# base.net
KiCad netlist of a schematic drawn in EAGLE
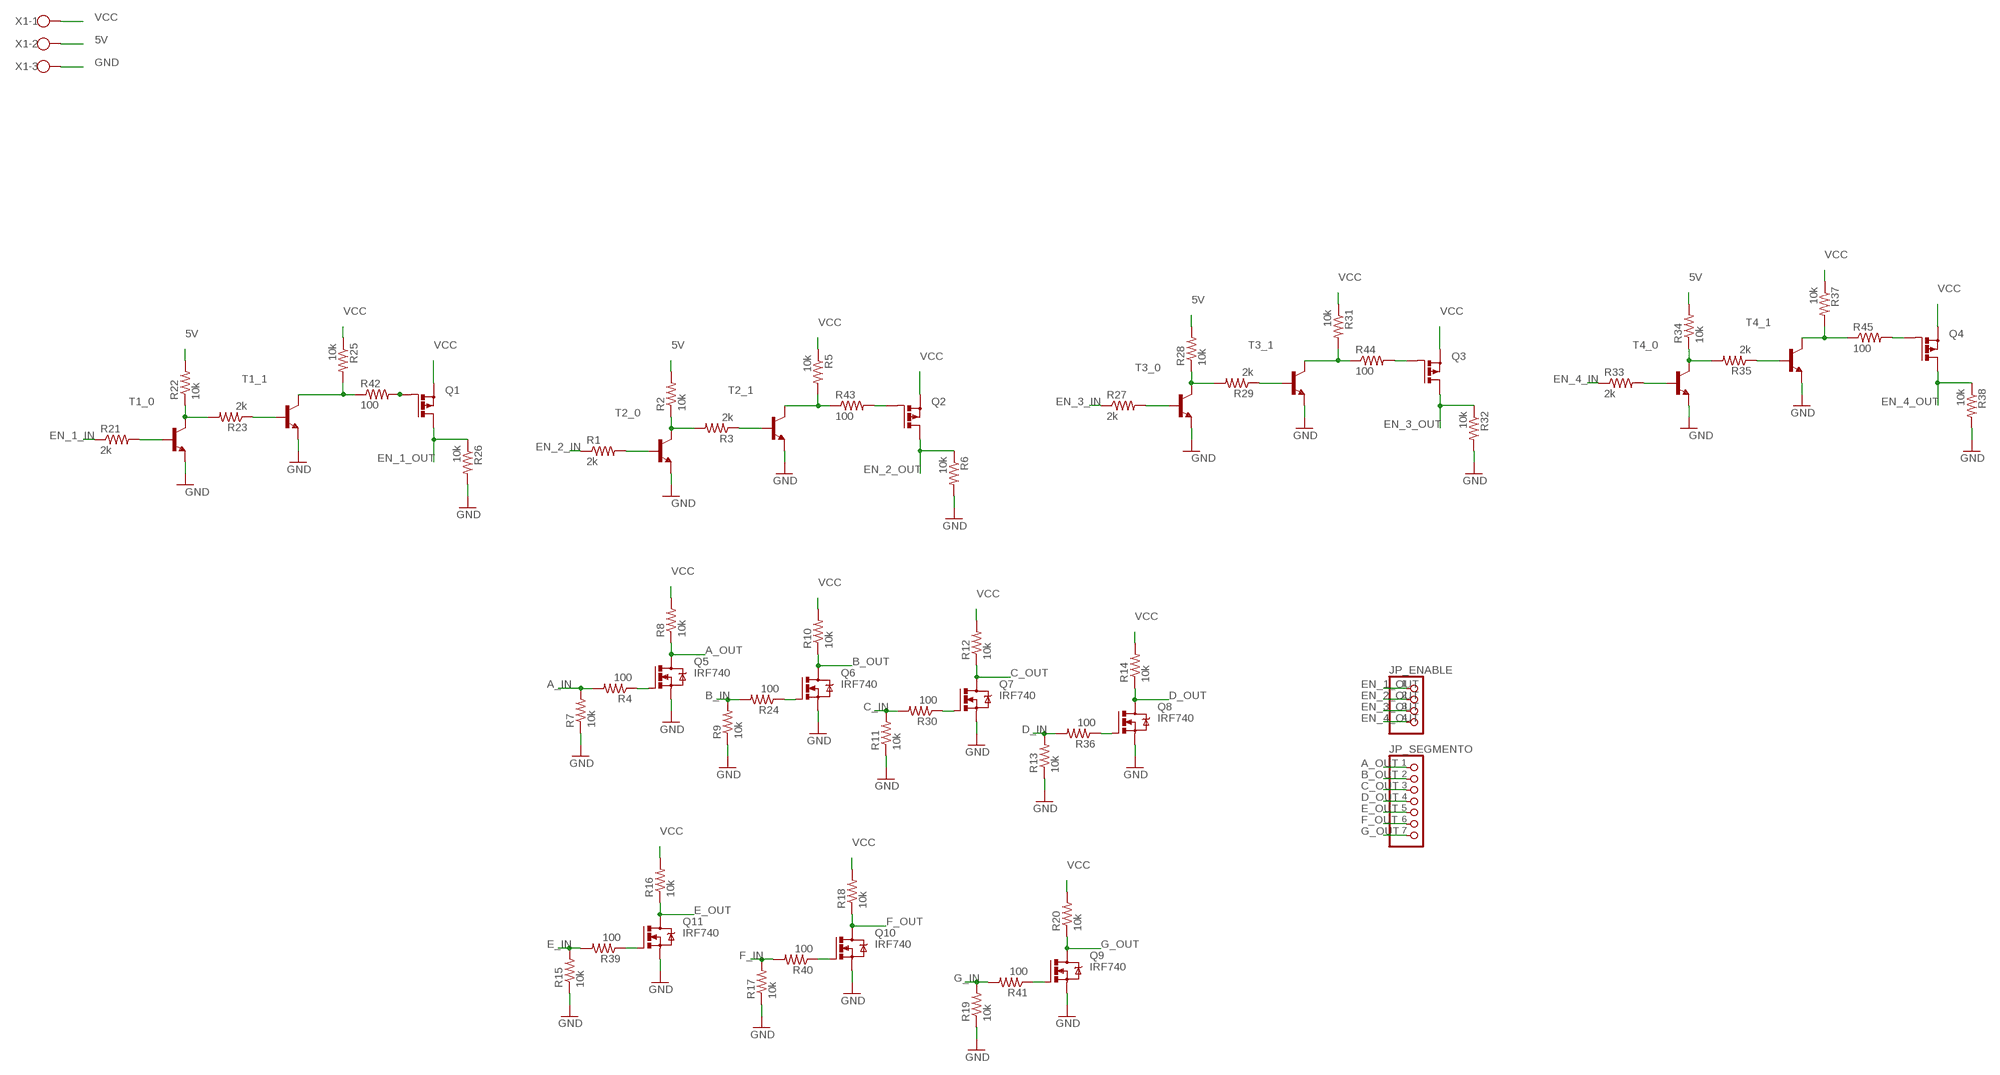
[diagram p0: schematic, sheet 1]

(export (version "E")
  (design (tool "Eeschema 10.0.6"))
  (components
    (comp (ref "JP_ENABLE")
      (value "PINHD-1X4")
      (footprint "eagle-import:1X04")
      (libsource (lib "eagle-import") (part "PINHD-1X4"))
    )
    (comp (ref "JP_SEGMENTO")
      (value "PINHD-1X7")
      (footprint "eagle-import:1X07")
      (libsource (lib "eagle-import") (part "PINHD-1X7"))
    )
    (comp (ref "Q1")
      (value "PMOSFET_PTO220BV")
      (footprint "eagle-import:TO220BV")
      (libsource (lib "eagle-import") (part "PMOSFET_PTO220BV"))
    )
    (comp (ref "Q2")
      (value "PMOSFET_PTO220BV")
      (footprint "eagle-import:TO220BV")
      (libsource (lib "eagle-import") (part "PMOSFET_PTO220BV"))
    )
    (comp (ref "Q3")
      (value "PMOSFET_PTO220BV")
      (footprint "eagle-import:TO220BV")
      (libsource (lib "eagle-import") (part "PMOSFET_PTO220BV"))
    )
    (comp (ref "Q4")
      (value "PMOSFET_PTO220BV")
      (footprint "eagle-import:TO220BV")
      (libsource (lib "eagle-import") (part "PMOSFET_PTO220BV"))
    )
    (comp (ref "Q5")
      (value "IRF740")
      (footprint "eagle-import:TO220BV")
      (libsource (lib "eagle-import") (part "IRF740"))
    )
    (comp (ref "Q6")
      (value "IRF740")
      (footprint "eagle-import:TO220BV")
      (libsource (lib "eagle-import") (part "IRF740"))
    )
    (comp (ref "Q7")
      (value "IRF740")
      (footprint "eagle-import:TO220BV")
      (libsource (lib "eagle-import") (part "IRF740"))
    )
    (comp (ref "Q8")
      (value "IRF740")
      (footprint "eagle-import:TO220BV")
      (libsource (lib "eagle-import") (part "IRF740"))
    )
    (comp (ref "Q9")
      (value "IRF740")
      (footprint "eagle-import:TO220BV")
      (libsource (lib "eagle-import") (part "IRF740"))
    )
    (comp (ref "Q10")
      (value "IRF740")
      (footprint "eagle-import:TO220BV")
      (libsource (lib "eagle-import") (part "IRF740"))
    )
    (comp (ref "Q11")
      (value "IRF740")
      (footprint "eagle-import:TO220BV")
      (libsource (lib "eagle-import") (part "IRF740"))
    )
    (comp (ref "R1")
      (value "2k")
      (footprint "eagle-import:0207_10")
      (libsource (lib "eagle-import") (part "R-US_0207/10"))
    )
    (comp (ref "R2")
      (value "10k")
      (footprint "eagle-import:0207_10")
      (libsource (lib "eagle-import") (part "R-US_0207/10"))
    )
    (comp (ref "R3")
      (value "2k")
      (footprint "eagle-import:0207_10")
      (libsource (lib "eagle-import") (part "R-US_0207/10"))
    )
    (comp (ref "R4")
      (value "100")
      (footprint "eagle-import:0207_10")
      (libsource (lib "eagle-import") (part "R-US_0207/10"))
    )
    (comp (ref "R5")
      (value "10k")
      (footprint "eagle-import:0207_10")
      (libsource (lib "eagle-import") (part "R-US_0207/10"))
    )
    (comp (ref "R6")
      (value "10k")
      (footprint "eagle-import:0207_10")
      (libsource (lib "eagle-import") (part "R-US_0207/10"))
    )
    (comp (ref "R7")
      (value "10k")
      (footprint "eagle-import:0207_10")
      (libsource (lib "eagle-import") (part "R-US_0207/10"))
    )
    (comp (ref "R8")
      (value "10k")
      (footprint "eagle-import:0207_10")
      (libsource (lib "eagle-import") (part "R-US_0207/10"))
    )
    (comp (ref "R9")
      (value "10k")
      (footprint "eagle-import:0207_10")
      (libsource (lib "eagle-import") (part "R-US_0207/10"))
    )
    (comp (ref "R10")
      (value "10k")
      (footprint "eagle-import:0207_10")
      (libsource (lib "eagle-import") (part "R-US_0207/10"))
    )
    (comp (ref "R11")
      (value "10k")
      (footprint "eagle-import:0207_10")
      (libsource (lib "eagle-import") (part "R-US_0207/10"))
    )
    (comp (ref "R12")
      (value "10k")
      (footprint "eagle-import:0207_10")
      (libsource (lib "eagle-import") (part "R-US_0207/10"))
    )
    (comp (ref "R13")
      (value "10k")
      (footprint "eagle-import:0207_10")
      (libsource (lib "eagle-import") (part "R-US_0207/10"))
    )
    (comp (ref "R14")
      (value "10k")
      (footprint "eagle-import:0207_10")
      (libsource (lib "eagle-import") (part "R-US_0207/10"))
    )
    (comp (ref "R15")
      (value "10k")
      (footprint "eagle-import:0207_10")
      (libsource (lib "eagle-import") (part "R-US_0207/10"))
    )
    (comp (ref "R16")
      (value "10k")
      (footprint "eagle-import:0207_10")
      (libsource (lib "eagle-import") (part "R-US_0207/10"))
    )
    (comp (ref "R17")
      (value "10k")
      (footprint "eagle-import:0207_10")
      (libsource (lib "eagle-import") (part "R-US_0207/10"))
    )
    (comp (ref "R18")
      (value "10k")
      (footprint "eagle-import:0207_10")
      (libsource (lib "eagle-import") (part "R-US_0207/10"))
    )
    (comp (ref "R19")
      (value "10k")
      (footprint "eagle-import:0207_10")
      (libsource (lib "eagle-import") (part "R-US_0207/10"))
    )
    (comp (ref "R20")
      (value "10k")
      (footprint "eagle-import:0207_10")
      (libsource (lib "eagle-import") (part "R-US_0207/10"))
    )
    (comp (ref "R21")
      (value "2k")
      (footprint "eagle-import:0207_10")
      (libsource (lib "eagle-import") (part "R-US_0207/10"))
    )
    (comp (ref "R22")
      (value "10k")
      (footprint "eagle-import:0207_10")
      (libsource (lib "eagle-import") (part "R-US_0207/10"))
    )
    (comp (ref "R23")
      (value "2k")
      (footprint "eagle-import:0207_10")
      (libsource (lib "eagle-import") (part "R-US_0207/10"))
    )
    (comp (ref "R24")
      (value "100")
      (footprint "eagle-import:0207_10")
      (libsource (lib "eagle-import") (part "R-US_0207/10"))
    )
    (comp (ref "R25")
      (value "10k")
      (footprint "eagle-import:0207_10")
      (libsource (lib "eagle-import") (part "R-US_0207/10"))
    )
    (comp (ref "R26")
      (value "10k")
      (footprint "eagle-import:0207_10")
      (libsource (lib "eagle-import") (part "R-US_0207/10"))
    )
    (comp (ref "R27")
      (value "2k")
      (footprint "eagle-import:0207_10")
      (libsource (lib "eagle-import") (part "R-US_0207/10"))
    )
    (comp (ref "R28")
      (value "10k")
      (footprint "eagle-import:0207_10")
      (libsource (lib "eagle-import") (part "R-US_0207/10"))
    )
    (comp (ref "R29")
      (value "2k")
      (footprint "eagle-import:0207_10")
      (libsource (lib "eagle-import") (part "R-US_0207/10"))
    )
    (comp (ref "R30")
      (value "100")
      (footprint "eagle-import:0207_10")
      (libsource (lib "eagle-import") (part "R-US_0207/10"))
    )
    (comp (ref "R31")
      (value "10k")
      (footprint "eagle-import:0207_10")
      (libsource (lib "eagle-import") (part "R-US_0207/10"))
    )
    (comp (ref "R32")
      (value "10k")
      (footprint "eagle-import:0207_10")
      (libsource (lib "eagle-import") (part "R-US_0207/10"))
    )
    (comp (ref "R33")
      (value "2k")
      (footprint "eagle-import:0207_10")
      (libsource (lib "eagle-import") (part "R-US_0207/10"))
    )
    (comp (ref "R34")
      (value "10k")
      (footprint "eagle-import:0207_10")
      (libsource (lib "eagle-import") (part "R-US_0207/10"))
    )
    (comp (ref "R35")
      (value "2k")
      (footprint "eagle-import:0207_10")
      (libsource (lib "eagle-import") (part "R-US_0207/10"))
    )
    (comp (ref "R36")
      (value "100")
      (footprint "eagle-import:0207_10")
      (libsource (lib "eagle-import") (part "R-US_0207/10"))
    )
    (comp (ref "R37")
      (value "10k")
      (footprint "eagle-import:0207_10")
      (libsource (lib "eagle-import") (part "R-US_0207/10"))
    )
    (comp (ref "R38")
      (value "10k")
      (footprint "eagle-import:0207_10")
      (libsource (lib "eagle-import") (part "R-US_0207/10"))
    )
    (comp (ref "R39")
      (value "100")
      (footprint "eagle-import:0207_10")
      (libsource (lib "eagle-import") (part "R-US_0207/10"))
    )
    (comp (ref "R40")
      (value "100")
      (footprint "eagle-import:0207_10")
      (libsource (lib "eagle-import") (part "R-US_0207/10"))
    )
    (comp (ref "R41")
      (value "100")
      (footprint "eagle-import:0207_10")
      (libsource (lib "eagle-import") (part "R-US_0207/10"))
    )
    (comp (ref "R42")
      (value "100")
      (footprint "eagle-import:0207_10")
      (libsource (lib "eagle-import") (part "R-US_0207/10"))
    )
    (comp (ref "R43")
      (value "100")
      (footprint "eagle-import:0207_10")
      (libsource (lib "eagle-import") (part "R-US_0207/10"))
    )
    (comp (ref "R44")
      (value "100")
      (footprint "eagle-import:0207_10")
      (libsource (lib "eagle-import") (part "R-US_0207/10"))
    )
    (comp (ref "R45")
      (value "100")
      (footprint "eagle-import:0207_10")
      (libsource (lib "eagle-import") (part "R-US_0207/10"))
    )
    (comp (ref "T1_0")
      (value "2N2222-NPN-TO92-EBC")
      (footprint "eagle-import:TO92-EBC")
      (libsource (lib "eagle-import") (part "-NPN-TO92-EBC2N2222"))
    )
    (comp (ref "T1_1")
      (value "2N2222-NPN-TO92-EBC")
      (footprint "eagle-import:TO92-EBC")
      (libsource (lib "eagle-import") (part "-NPN-TO92-EBC2N2222"))
    )
    (comp (ref "T2_0")
      (value "2N2222-NPN-TO92-EBC")
      (footprint "eagle-import:TO92-EBC")
      (libsource (lib "eagle-import") (part "-NPN-TO92-EBC2N2222"))
    )
    (comp (ref "T2_1")
      (value "2N2222-NPN-TO92-EBC")
      (footprint "eagle-import:TO92-EBC")
      (libsource (lib "eagle-import") (part "-NPN-TO92-EBC2N2222"))
    )
    (comp (ref "T3_0")
      (value "2N2222-NPN-TO92-EBC")
      (footprint "eagle-import:TO92-EBC")
      (libsource (lib "eagle-import") (part "-NPN-TO92-EBC2N2222"))
    )
    (comp (ref "T3_1")
      (value "2N2222-NPN-TO92-EBC")
      (footprint "eagle-import:TO92-EBC")
      (libsource (lib "eagle-import") (part "-NPN-TO92-EBC2N2222"))
    )
    (comp (ref "T4_0")
      (value "2N2222-NPN-TO92-EBC")
      (footprint "eagle-import:TO92-EBC")
      (libsource (lib "eagle-import") (part "-NPN-TO92-EBC2N2222"))
    )
    (comp (ref "T4_1")
      (value "2N2222-NPN-TO92-EBC")
      (footprint "eagle-import:TO92-EBC")
      (libsource (lib "eagle-import") (part "-NPN-TO92-EBC2N2222"))
    )
    (comp (ref "X1")
      (value "W237-103")
      (footprint "eagle-import:W237-103")
      (fields (field (name "MPN") "237-103"))
      (libsource (lib "eagle-import") (part "W237-103"))
    )
  )
  (nets
    (net (code "1") (name "/5V") (class "Default")
      (node (ref "R2") (pin "2") (pinfunction "2_2") (pintype "passive"))
      (node (ref "R22") (pin "2") (pinfunction "2_2") (pintype "passive"))
      (node (ref "R28") (pin "2") (pinfunction "2_2") (pintype "passive"))
      (node (ref "R34") (pin "2") (pinfunction "2_2") (pintype "passive"))
      (node (ref "X1") (pin "2") (pinfunction "KL_2") (pintype "passive"))
    )
    (net (code "2") (name "/A_IN") (class "Default")
      (node (ref "R4") (pin "2") (pinfunction "2_2") (pintype "passive"))
      (node (ref "R7") (pin "2") (pinfunction "2_2") (pintype "passive"))
    )
    (net (code "3") (name "/A_OUT") (class "Default")
      (node (ref "JP_SEGMENTO") (pin "1") (pinfunction "1_1") (pintype "passive"))
      (node (ref "Q5") (pin "D") (pinfunction "D_D") (pintype "passive"))
      (node (ref "R8") (pin "1") (pinfunction "1_1") (pintype "passive"))
    )
    (net (code "4") (name "/B_IN") (class "Default")
      (node (ref "R24") (pin "2") (pinfunction "2_2") (pintype "passive"))
      (node (ref "R9") (pin "2") (pinfunction "2_2") (pintype "passive"))
    )
    (net (code "5") (name "/B_OUT") (class "Default")
      (node (ref "JP_SEGMENTO") (pin "2") (pinfunction "2_2") (pintype "passive"))
      (node (ref "Q6") (pin "D") (pinfunction "D_D") (pintype "passive"))
      (node (ref "R10") (pin "1") (pinfunction "1_1") (pintype "passive"))
    )
    (net (code "6") (name "/C_IN") (class "Default")
      (node (ref "R11") (pin "2") (pinfunction "2_2") (pintype "passive"))
      (node (ref "R30") (pin "2") (pinfunction "2_2") (pintype "passive"))
    )
    (net (code "7") (name "/C_OUT") (class "Default")
      (node (ref "JP_SEGMENTO") (pin "3") (pinfunction "3_3") (pintype "passive"))
      (node (ref "Q7") (pin "D") (pinfunction "D_D") (pintype "passive"))
      (node (ref "R12") (pin "1") (pinfunction "1_1") (pintype "passive"))
    )
    (net (code "8") (name "/D_IN") (class "Default")
      (node (ref "R13") (pin "2") (pinfunction "2_2") (pintype "passive"))
      (node (ref "R36") (pin "2") (pinfunction "2_2") (pintype "passive"))
    )
    (net (code "9") (name "/D_OUT") (class "Default")
      (node (ref "JP_SEGMENTO") (pin "4") (pinfunction "4_4") (pintype "passive"))
      (node (ref "Q8") (pin "D") (pinfunction "D_D") (pintype "passive"))
      (node (ref "R14") (pin "1") (pinfunction "1_1") (pintype "passive"))
    )
    (net (code "10") (name "/EN_1_IN") (class "Default")
      (node (ref "R21") (pin "1") (pinfunction "1_1") (pintype "passive"))
    )
    (net (code "11") (name "/EN_1_OUT") (class "Default")
      (node (ref "JP_ENABLE") (pin "1") (pinfunction "1_1") (pintype "passive"))
      (node (ref "Q1") (pin "D") (pinfunction "D_D") (pintype "passive"))
      (node (ref "R26") (pin "1") (pinfunction "1_1") (pintype "passive"))
    )
    (net (code "12") (name "/EN_2_IN") (class "Default")
      (node (ref "R1") (pin "1") (pinfunction "1_1") (pintype "passive"))
    )
    (net (code "13") (name "/EN_2_OUT") (class "Default")
      (node (ref "JP_ENABLE") (pin "2") (pinfunction "2_2") (pintype "passive"))
      (node (ref "Q2") (pin "D") (pinfunction "D_D") (pintype "passive"))
      (node (ref "R6") (pin "1") (pinfunction "1_1") (pintype "passive"))
    )
    (net (code "14") (name "/EN_3_IN") (class "Default")
      (node (ref "R27") (pin "1") (pinfunction "1_1") (pintype "passive"))
    )
    (net (code "15") (name "/EN_3_OUT") (class "Default")
      (node (ref "JP_ENABLE") (pin "3") (pinfunction "3_3") (pintype "passive"))
      (node (ref "Q3") (pin "D") (pinfunction "D_D") (pintype "passive"))
      (node (ref "R32") (pin "1") (pinfunction "1_1") (pintype "passive"))
    )
    (net (code "16") (name "/EN_4_IN") (class "Default")
      (node (ref "R33") (pin "1") (pinfunction "1_1") (pintype "passive"))
    )
    (net (code "17") (name "/EN_4_OUT") (class "Default")
      (node (ref "JP_ENABLE") (pin "4") (pinfunction "4_4") (pintype "passive"))
      (node (ref "Q4") (pin "D") (pinfunction "D_D") (pintype "passive"))
      (node (ref "R38") (pin "1") (pinfunction "1_1") (pintype "passive"))
    )
    (net (code "18") (name "/E_IN") (class "Default")
      (node (ref "R15") (pin "2") (pinfunction "2_2") (pintype "passive"))
      (node (ref "R39") (pin "2") (pinfunction "2_2") (pintype "passive"))
    )
    (net (code "19") (name "/E_OUT") (class "Default")
      (node (ref "JP_SEGMENTO") (pin "5") (pinfunction "5_5") (pintype "passive"))
      (node (ref "Q11") (pin "D") (pinfunction "D_D") (pintype "passive"))
      (node (ref "R16") (pin "1") (pinfunction "1_1") (pintype "passive"))
    )
    (net (code "20") (name "/F_IN") (class "Default")
      (node (ref "R17") (pin "2") (pinfunction "2_2") (pintype "passive"))
      (node (ref "R40") (pin "2") (pinfunction "2_2") (pintype "passive"))
    )
    (net (code "21") (name "/F_OUT") (class "Default")
      (node (ref "JP_SEGMENTO") (pin "6") (pinfunction "6_6") (pintype "passive"))
      (node (ref "Q10") (pin "D") (pinfunction "D_D") (pintype "passive"))
      (node (ref "R18") (pin "1") (pinfunction "1_1") (pintype "passive"))
    )
    (net (code "22") (name "/G_IN") (class "Default")
      (node (ref "R19") (pin "2") (pinfunction "2_2") (pintype "passive"))
      (node (ref "R41") (pin "2") (pinfunction "2_2") (pintype "passive"))
    )
    (net (code "23") (name "/G_OUT") (class "Default")
      (node (ref "JP_SEGMENTO") (pin "7") (pinfunction "7_7") (pintype "passive"))
      (node (ref "Q9") (pin "D") (pinfunction "D_D") (pintype "passive"))
      (node (ref "R20") (pin "1") (pinfunction "1_1") (pintype "passive"))
    )
    (net (code "24") (name "/VCC") (class "Default")
      (node (ref "Q1") (pin "S") (pinfunction "S_S") (pintype "passive"))
      (node (ref "Q2") (pin "S") (pinfunction "S_S") (pintype "passive"))
      (node (ref "Q3") (pin "S") (pinfunction "S_S") (pintype "passive"))
      (node (ref "Q4") (pin "S") (pinfunction "S_S") (pintype "passive"))
      (node (ref "R10") (pin "2") (pinfunction "2_2") (pintype "passive"))
      (node (ref "R12") (pin "2") (pinfunction "2_2") (pintype "passive"))
      (node (ref "R14") (pin "2") (pinfunction "2_2") (pintype "passive"))
      (node (ref "R16") (pin "2") (pinfunction "2_2") (pintype "passive"))
      (node (ref "R18") (pin "2") (pinfunction "2_2") (pintype "passive"))
      (node (ref "R20") (pin "2") (pinfunction "2_2") (pintype "passive"))
      (node (ref "R25") (pin "1") (pinfunction "1_1") (pintype "passive"))
      (node (ref "R31") (pin "1") (pinfunction "1_1") (pintype "passive"))
      (node (ref "R37") (pin "1") (pinfunction "1_1") (pintype "passive"))
      (node (ref "R5") (pin "1") (pinfunction "1_1") (pintype "passive"))
      (node (ref "R8") (pin "2") (pinfunction "2_2") (pintype "passive"))
      (node (ref "X1") (pin "1") (pinfunction "KL_1") (pintype "passive"))
    )
    (net (code "25") (name "GND") (class "Default")
      (node (ref "Q10") (pin "S") (pinfunction "S_S") (pintype "passive"))
      (node (ref "Q11") (pin "S") (pinfunction "S_S") (pintype "passive"))
      (node (ref "Q5") (pin "S") (pinfunction "S_S") (pintype "passive"))
      (node (ref "Q6") (pin "S") (pinfunction "S_S") (pintype "passive"))
      (node (ref "Q7") (pin "S") (pinfunction "S_S") (pintype "passive"))
      (node (ref "Q8") (pin "S") (pinfunction "S_S") (pintype "passive"))
      (node (ref "Q9") (pin "S") (pinfunction "S_S") (pintype "passive"))
      (node (ref "R11") (pin "1") (pinfunction "1_1") (pintype "passive"))
      (node (ref "R13") (pin "1") (pinfunction "1_1") (pintype "passive"))
      (node (ref "R15") (pin "1") (pinfunction "1_1") (pintype "passive"))
      (node (ref "R17") (pin "1") (pinfunction "1_1") (pintype "passive"))
      (node (ref "R19") (pin "1") (pinfunction "1_1") (pintype "passive"))
      (node (ref "R26") (pin "2") (pinfunction "2_2") (pintype "passive"))
      (node (ref "R32") (pin "2") (pinfunction "2_2") (pintype "passive"))
      (node (ref "R38") (pin "2") (pinfunction "2_2") (pintype "passive"))
      (node (ref "R6") (pin "2") (pinfunction "2_2") (pintype "passive"))
      (node (ref "R7") (pin "1") (pinfunction "1_1") (pintype "passive"))
      (node (ref "R9") (pin "1") (pinfunction "1_1") (pintype "passive"))
      (node (ref "T1_0") (pin "E") (pinfunction "E_E") (pintype "passive"))
      (node (ref "T1_1") (pin "E") (pinfunction "E_E") (pintype "passive"))
      (node (ref "T2_0") (pin "E") (pinfunction "E_E") (pintype "passive"))
      (node (ref "T2_1") (pin "E") (pinfunction "E_E") (pintype "passive"))
      (node (ref "T3_0") (pin "E") (pinfunction "E_E") (pintype "passive"))
      (node (ref "T3_1") (pin "E") (pinfunction "E_E") (pintype "passive"))
      (node (ref "T4_0") (pin "E") (pinfunction "E_E") (pintype "passive"))
      (node (ref "T4_1") (pin "E") (pinfunction "E_E") (pintype "passive"))
      (node (ref "X1") (pin "3") (pinfunction "KL_3") (pintype "passive"))
    )
    (net (code "26") (name "Net-(Q1-PadG)") (class "Default")
      (node (ref "Q1") (pin "G") (pinfunction "G_G") (pintype "passive"))
      (node (ref "R42") (pin "2") (pinfunction "2_2") (pintype "passive"))
    )
    (net (code "27") (name "Net-(Q2-PadG)") (class "Default")
      (node (ref "Q2") (pin "G") (pinfunction "G_G") (pintype "passive"))
      (node (ref "R43") (pin "2") (pinfunction "2_2") (pintype "passive"))
    )
    (net (code "28") (name "Net-(Q3-PadG)") (class "Default")
      (node (ref "Q3") (pin "G") (pinfunction "G_G") (pintype "passive"))
      (node (ref "R44") (pin "2") (pinfunction "2_2") (pintype "passive"))
    )
    (net (code "29") (name "Net-(Q4-PadG)") (class "Default")
      (node (ref "Q4") (pin "G") (pinfunction "G_G") (pintype "passive"))
      (node (ref "R45") (pin "2") (pinfunction "2_2") (pintype "passive"))
    )
    (net (code "30") (name "Net-(Q5-PadG)") (class "Default")
      (node (ref "Q5") (pin "G") (pinfunction "G_G") (pintype "passive"))
      (node (ref "R4") (pin "1") (pinfunction "1_1") (pintype "passive"))
    )
    (net (code "31") (name "Net-(Q6-PadG)") (class "Default")
      (node (ref "Q6") (pin "G") (pinfunction "G_G") (pintype "passive"))
      (node (ref "R24") (pin "1") (pinfunction "1_1") (pintype "passive"))
    )
    (net (code "32") (name "Net-(Q7-PadG)") (class "Default")
      (node (ref "Q7") (pin "G") (pinfunction "G_G") (pintype "passive"))
      (node (ref "R30") (pin "1") (pinfunction "1_1") (pintype "passive"))
    )
    (net (code "33") (name "Net-(Q8-PadG)") (class "Default")
      (node (ref "Q8") (pin "G") (pinfunction "G_G") (pintype "passive"))
      (node (ref "R36") (pin "1") (pinfunction "1_1") (pintype "passive"))
    )
    (net (code "34") (name "Net-(Q9-PadG)") (class "Default")
      (node (ref "Q9") (pin "G") (pinfunction "G_G") (pintype "passive"))
      (node (ref "R41") (pin "1") (pinfunction "1_1") (pintype "passive"))
    )
    (net (code "35") (name "Net-(Q10-PadG)") (class "Default")
      (node (ref "Q10") (pin "G") (pinfunction "G_G") (pintype "passive"))
      (node (ref "R40") (pin "1") (pinfunction "1_1") (pintype "passive"))
    )
    (net (code "36") (name "Net-(Q11-PadG)") (class "Default")
      (node (ref "Q11") (pin "G") (pinfunction "G_G") (pintype "passive"))
      (node (ref "R39") (pin "1") (pinfunction "1_1") (pintype "passive"))
    )
    (net (code "37") (name "Net-(R1-Pad2)") (class "Default")
      (node (ref "R1") (pin "2") (pinfunction "2_2") (pintype "passive"))
      (node (ref "T2_0") (pin "B") (pinfunction "B_B") (pintype "passive"))
    )
    (net (code "38") (name "Net-(R2-Pad1)") (class "Default")
      (node (ref "R2") (pin "1") (pinfunction "1_1") (pintype "passive"))
      (node (ref "R3") (pin "2") (pinfunction "2_2") (pintype "passive"))
      (node (ref "T2_0") (pin "C") (pinfunction "C_C") (pintype "passive"))
    )
    (net (code "39") (name "Net-(R3-Pad1)") (class "Default")
      (node (ref "R3") (pin "1") (pinfunction "1_1") (pintype "passive"))
      (node (ref "T2_1") (pin "B") (pinfunction "B_B") (pintype "passive"))
    )
    (net (code "40") (name "Net-(R21-Pad2)") (class "Default")
      (node (ref "R21") (pin "2") (pinfunction "2_2") (pintype "passive"))
      (node (ref "T1_0") (pin "B") (pinfunction "B_B") (pintype "passive"))
    )
    (net (code "41") (name "Net-(R22-Pad1)") (class "Default")
      (node (ref "R22") (pin "1") (pinfunction "1_1") (pintype "passive"))
      (node (ref "R23") (pin "2") (pinfunction "2_2") (pintype "passive"))
      (node (ref "T1_0") (pin "C") (pinfunction "C_C") (pintype "passive"))
    )
    (net (code "42") (name "Net-(R23-Pad1)") (class "Default")
      (node (ref "R23") (pin "1") (pinfunction "1_1") (pintype "passive"))
      (node (ref "T1_1") (pin "B") (pinfunction "B_B") (pintype "passive"))
    )
    (net (code "43") (name "Net-(R25-Pad2)") (class "Default")
      (node (ref "R25") (pin "2") (pinfunction "2_2") (pintype "passive"))
      (node (ref "R42") (pin "1") (pinfunction "1_1") (pintype "passive"))
      (node (ref "T1_1") (pin "C") (pinfunction "C_C") (pintype "passive"))
    )
    (net (code "44") (name "Net-(R27-Pad2)") (class "Default")
      (node (ref "R27") (pin "2") (pinfunction "2_2") (pintype "passive"))
      (node (ref "T3_0") (pin "B") (pinfunction "B_B") (pintype "passive"))
    )
    (net (code "45") (name "Net-(R28-Pad1)") (class "Default")
      (node (ref "R28") (pin "1") (pinfunction "1_1") (pintype "passive"))
      (node (ref "R29") (pin "2") (pinfunction "2_2") (pintype "passive"))
      (node (ref "T3_0") (pin "C") (pinfunction "C_C") (pintype "passive"))
    )
    (net (code "46") (name "Net-(R29-Pad1)") (class "Default")
      (node (ref "R29") (pin "1") (pinfunction "1_1") (pintype "passive"))
      (node (ref "T3_1") (pin "B") (pinfunction "B_B") (pintype "passive"))
    )
    (net (code "47") (name "Net-(R31-Pad2)") (class "Default")
      (node (ref "R31") (pin "2") (pinfunction "2_2") (pintype "passive"))
      (node (ref "R44") (pin "1") (pinfunction "1_1") (pintype "passive"))
      (node (ref "T3_1") (pin "C") (pinfunction "C_C") (pintype "passive"))
    )
    (net (code "48") (name "Net-(R33-Pad2)") (class "Default")
      (node (ref "R33") (pin "2") (pinfunction "2_2") (pintype "passive"))
      (node (ref "T4_0") (pin "B") (pinfunction "B_B") (pintype "passive"))
    )
    (net (code "49") (name "Net-(R34-Pad1)") (class "Default")
      (node (ref "R34") (pin "1") (pinfunction "1_1") (pintype "passive"))
      (node (ref "R35") (pin "2") (pinfunction "2_2") (pintype "passive"))
      (node (ref "T4_0") (pin "C") (pinfunction "C_C") (pintype "passive"))
    )
    (net (code "50") (name "Net-(R35-Pad1)") (class "Default")
      (node (ref "R35") (pin "1") (pinfunction "1_1") (pintype "passive"))
      (node (ref "T4_1") (pin "B") (pinfunction "B_B") (pintype "passive"))
    )
    (net (code "51") (name "Net-(R37-Pad2)") (class "Default")
      (node (ref "R37") (pin "2") (pinfunction "2_2") (pintype "passive"))
      (node (ref "R45") (pin "1") (pinfunction "1_1") (pintype "passive"))
      (node (ref "T4_1") (pin "C") (pinfunction "C_C") (pintype "passive"))
    )
    (net (code "52") (name "Net-(R43-Pad1)") (class "Default")
      (node (ref "R43") (pin "1") (pinfunction "1_1") (pintype "passive"))
      (node (ref "R5") (pin "2") (pinfunction "2_2") (pintype "passive"))
      (node (ref "T2_1") (pin "C") (pinfunction "C_C") (pintype "passive"))
    )
  )
)
